# main.net
KiCad netlist of a schematic drawn in Altium Designer
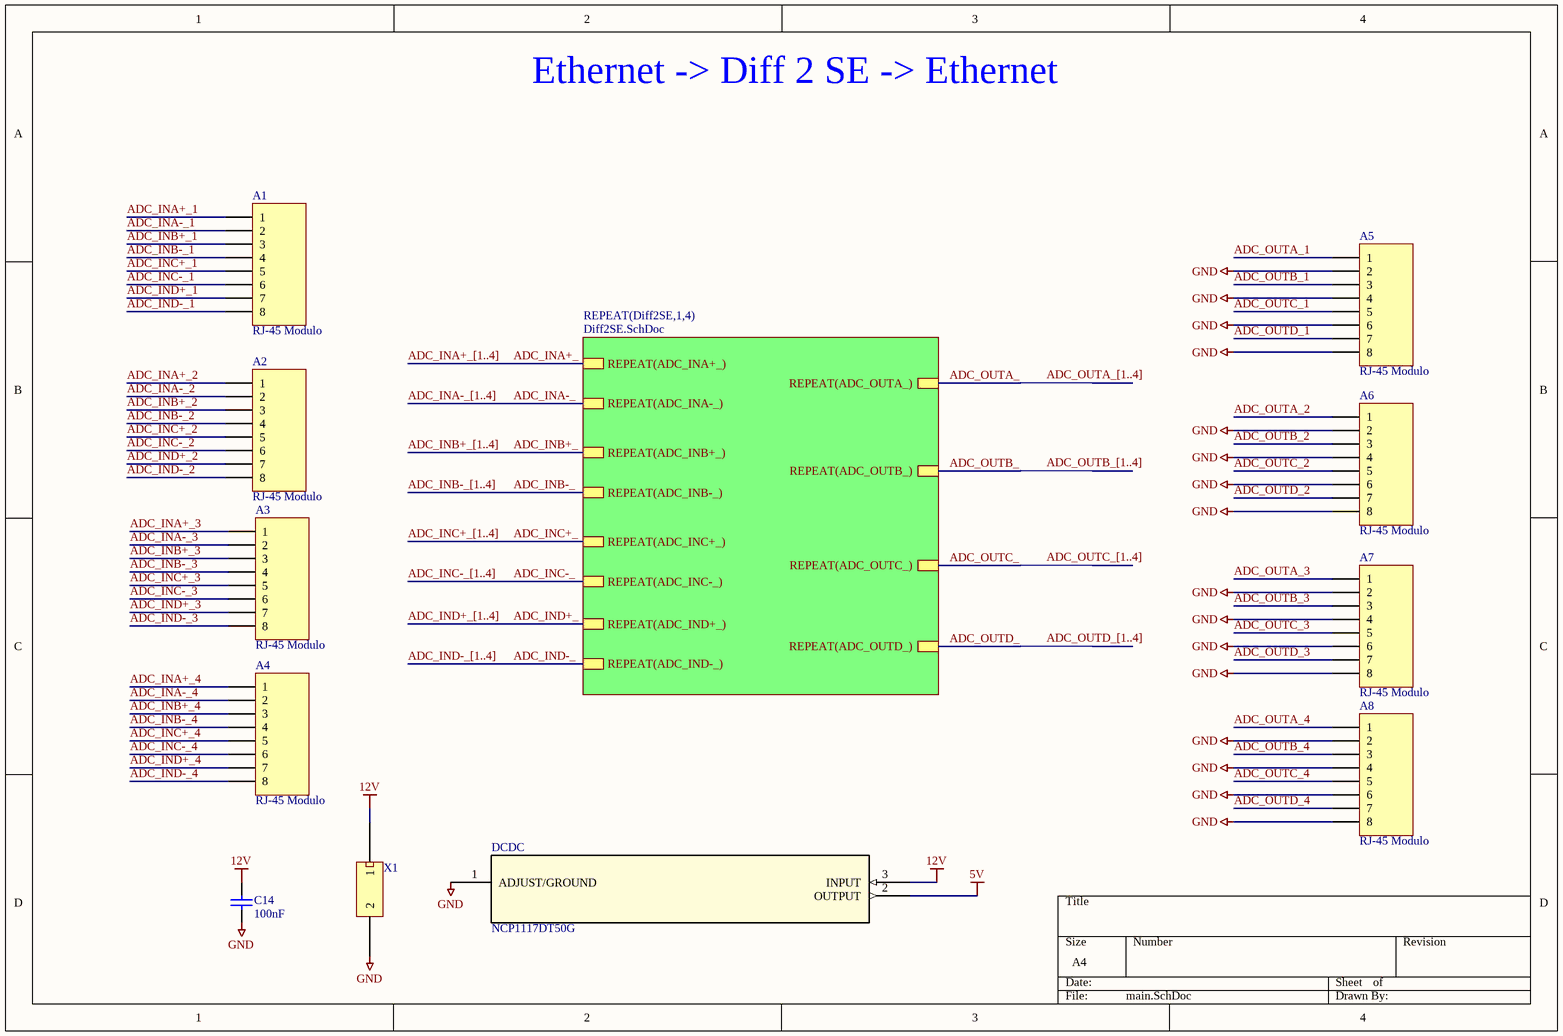
[diagram p0: main.SchDoc]

(export (version "E")
  (design (tool "Eeschema 10.0.6"))
  (components
    (comp (ref "A1")
      (value "RJ-45 Modulo")
      (footprint "RJ45_RJHSE5E80")
      (description "Modulo RJ-45 RJHSE5E80")
      (fields
        (field (name "MANUFACTURER") "Amphenol Commercial")
        (field (name "MANUFACTURER PART NUMBER") "RJHSE5E80")
        (field (name "PUBLISHER") "Altium Limited")
      )
      (libsource (lib "Schlib1") (part "RJ45_RJHSE5E80"))
    )
    (comp (ref "A2")
      (value "RJ-45 Modulo")
      (footprint "RJ45_RJHSE5E80")
      (description "Modulo RJ-45 RJHSE5E80")
      (fields
        (field (name "MANUFACTURER") "Amphenol Commercial")
        (field (name "MANUFACTURER PART NUMBER") "RJHSE5E80")
        (field (name "PUBLISHER") "Altium Limited")
      )
      (libsource (lib "Schlib1") (part "RJ45_RJHSE5E80"))
    )
    (comp (ref "A3")
      (value "RJ-45 Modulo")
      (footprint "RJ45_RJHSE5E80")
      (description "Modulo RJ-45 RJHSE5E80")
      (fields
        (field (name "MANUFACTURER") "Amphenol Commercial")
        (field (name "MANUFACTURER PART NUMBER") "RJHSE5E80")
        (field (name "PUBLISHER") "Altium Limited")
      )
      (libsource (lib "Schlib1") (part "RJ45_RJHSE5E80"))
    )
    (comp (ref "A4")
      (value "RJ-45 Modulo")
      (footprint "RJ45_RJHSE5E80")
      (description "Modulo RJ-45 RJHSE5E80")
      (fields
        (field (name "MANUFACTURER") "Amphenol Commercial")
        (field (name "MANUFACTURER PART NUMBER") "RJHSE5E80")
        (field (name "PUBLISHER") "Altium Limited")
      )
      (libsource (lib "Schlib1") (part "RJ45_RJHSE5E80"))
    )
    (comp (ref "A5")
      (value "RJ-45 Modulo")
      (footprint "RJ45_RJHSE5E80")
      (description "Modulo RJ-45 RJHSE5E80")
      (fields
        (field (name "MANUFACTURER") "Amphenol Commercial")
        (field (name "MANUFACTURER PART NUMBER") "RJHSE5E80")
        (field (name "PUBLISHER") "Altium Limited")
      )
      (libsource (lib "Schlib1") (part "RJ45_RJHSE5E80"))
    )
    (comp (ref "A6")
      (value "RJ-45 Modulo")
      (footprint "RJ45_RJHSE5E80")
      (description "Modulo RJ-45 RJHSE5E80")
      (fields
        (field (name "MANUFACTURER") "Amphenol Commercial")
        (field (name "MANUFACTURER PART NUMBER") "RJHSE5E80")
        (field (name "PUBLISHER") "Altium Limited")
      )
      (libsource (lib "Schlib1") (part "RJ45_RJHSE5E80"))
    )
    (comp (ref "A7")
      (value "RJ-45 Modulo")
      (footprint "RJ45_RJHSE5E80")
      (description "Modulo RJ-45 RJHSE5E80")
      (fields
        (field (name "MANUFACTURER") "Amphenol Commercial")
        (field (name "MANUFACTURER PART NUMBER") "RJHSE5E80")
        (field (name "PUBLISHER") "Altium Limited")
      )
      (libsource (lib "Schlib1") (part "RJ45_RJHSE5E80"))
    )
    (comp (ref "A8")
      (value "RJ-45 Modulo")
      (footprint "RJ45_RJHSE5E80")
      (description "Modulo RJ-45 RJHSE5E80")
      (fields
        (field (name "MANUFACTURER") "Amphenol Commercial")
        (field (name "MANUFACTURER PART NUMBER") "RJHSE5E80")
        (field (name "PUBLISHER") "Altium Limited")
      )
      (libsource (lib "Schlib1") (part "RJ45_RJHSE5E80"))
    )
    (comp (ref "C14")
      (value "100nF")
      (footprint "CAP_0805")
      (description "0.1µF ±10% 50V Ceramic Capacitor X7R 0805 (2012 Metric)")
      (fields (field (name "MF") "KEMET") (field (name "CREATED") "2020_06_15_DAarancibia"))
      (libsource (lib "Schlib1") (part "Cap_0805"))
    )
    (comp (ref "DCDC")
      (value "NCP1117DT50G")
      (footprint "DPAK_ONS")
      (description "No Description Available")
      (libsource (lib "Schlib1") (part "NCP1117DT50G"))
    )
    (comp (ref "X1")
      (value "Connector 2x1 R/A")
      (footprint "CON_WR-MPC4-649002227222")
      (description "Connector Header Through Hole, Right Angle 2 position 0.165\" (4.20mm)")
      (fields
        (field (name "MF") "Würth Elektronik")
        (field (name "MPN") "649002227222")
        (field (name "CREATED") "2020_06_14_DArancibia")
      )
      (libsource (lib "Schlib1") (part "Con_WR-MPC4_2x1"))
    )
  )
  (nets
    (net (code "2") (name "/ADC_INA+_1") (class "Default")
      (node (ref "A1") (pin "1") (pinfunction "1_1") (pintype "passive"))
    )
    (net (code "3") (name "/ADC_INA+_2") (class "Default")
      (node (ref "A2") (pin "1") (pinfunction "1_1") (pintype "passive"))
    )
    (net (code "4") (name "/ADC_INA+_3") (class "Default")
      (node (ref "A3") (pin "1") (pinfunction "1_1") (pintype "passive"))
    )
    (net (code "5") (name "/ADC_INA+_4") (class "Default")
      (node (ref "A4") (pin "1") (pinfunction "1_1") (pintype "passive"))
    )
    (net (code "8") (name "/ADC_INA-_1") (class "Default")
      (node (ref "A1") (pin "2") (pinfunction "2_2") (pintype "passive"))
    )
    (net (code "9") (name "/ADC_INA-_2") (class "Default")
      (node (ref "A2") (pin "2") (pinfunction "2_2") (pintype "passive"))
    )
    (net (code "10") (name "/ADC_INA-_3") (class "Default")
      (node (ref "A3") (pin "2") (pinfunction "2_2") (pintype "passive"))
    )
    (net (code "11") (name "/ADC_INA-_4") (class "Default")
      (node (ref "A4") (pin "2") (pinfunction "2_2") (pintype "passive"))
    )
    (net (code "14") (name "/ADC_INB+_1") (class "Default")
      (node (ref "A1") (pin "3") (pinfunction "3_3") (pintype "passive"))
    )
    (net (code "15") (name "/ADC_INB+_2") (class "Default")
      (node (ref "A2") (pin "3") (pinfunction "3_3") (pintype "passive"))
    )
    (net (code "16") (name "/ADC_INB+_3") (class "Default")
      (node (ref "A3") (pin "3") (pinfunction "3_3") (pintype "passive"))
    )
    (net (code "17") (name "/ADC_INB+_4") (class "Default")
      (node (ref "A4") (pin "3") (pinfunction "3_3") (pintype "passive"))
    )
    (net (code "20") (name "/ADC_INB-_1") (class "Default")
      (node (ref "A1") (pin "4") (pinfunction "4_4") (pintype "passive"))
    )
    (net (code "21") (name "/ADC_INB-_2") (class "Default")
      (node (ref "A2") (pin "4") (pinfunction "4_4") (pintype "passive"))
    )
    (net (code "22") (name "/ADC_INB-_3") (class "Default")
      (node (ref "A3") (pin "4") (pinfunction "4_4") (pintype "passive"))
    )
    (net (code "23") (name "/ADC_INB-_4") (class "Default")
      (node (ref "A4") (pin "4") (pinfunction "4_4") (pintype "passive"))
    )
    (net (code "26") (name "/ADC_INC+_1") (class "Default")
      (node (ref "A1") (pin "5") (pinfunction "5_5") (pintype "passive"))
    )
    (net (code "27") (name "/ADC_INC+_2") (class "Default")
      (node (ref "A2") (pin "5") (pinfunction "5_5") (pintype "passive"))
    )
    (net (code "28") (name "/ADC_INC+_3") (class "Default")
      (node (ref "A3") (pin "5") (pinfunction "5_5") (pintype "passive"))
    )
    (net (code "29") (name "/ADC_INC+_4") (class "Default")
      (node (ref "A4") (pin "5") (pinfunction "5_5") (pintype "passive"))
    )
    (net (code "32") (name "/ADC_INC-_1") (class "Default")
      (node (ref "A1") (pin "6") (pinfunction "6_6") (pintype "passive"))
    )
    (net (code "33") (name "/ADC_INC-_2") (class "Default")
      (node (ref "A2") (pin "6") (pinfunction "6_6") (pintype "passive"))
    )
    (net (code "34") (name "/ADC_INC-_3") (class "Default")
      (node (ref "A3") (pin "6") (pinfunction "6_6") (pintype "passive"))
    )
    (net (code "35") (name "/ADC_INC-_4") (class "Default")
      (node (ref "A4") (pin "6") (pinfunction "6_6") (pintype "passive"))
    )
    (net (code "38") (name "/ADC_IND+_1") (class "Default")
      (node (ref "A1") (pin "7") (pinfunction "7_7") (pintype "passive"))
    )
    (net (code "39") (name "/ADC_IND+_2") (class "Default")
      (node (ref "A2") (pin "7") (pinfunction "7_7") (pintype "passive"))
    )
    (net (code "40") (name "/ADC_IND+_3") (class "Default")
      (node (ref "A3") (pin "7") (pinfunction "7_7") (pintype "passive"))
    )
    (net (code "41") (name "/ADC_IND+_4") (class "Default")
      (node (ref "A4") (pin "7") (pinfunction "7_7") (pintype "passive"))
    )
    (net (code "44") (name "/ADC_IND-_1") (class "Default")
      (node (ref "A1") (pin "8") (pinfunction "8_8") (pintype "passive"))
    )
    (net (code "45") (name "/ADC_IND-_2") (class "Default")
      (node (ref "A2") (pin "8") (pinfunction "8_8") (pintype "passive"))
    )
    (net (code "46") (name "/ADC_IND-_3") (class "Default")
      (node (ref "A3") (pin "8") (pinfunction "8_8") (pintype "passive"))
    )
    (net (code "47") (name "/ADC_IND-_4") (class "Default")
      (node (ref "A4") (pin "8") (pinfunction "8_8") (pintype "passive"))
    )
    (net (code "50") (name "/ADC_OUTA_1") (class "Default")
      (node (ref "A5") (pin "1") (pinfunction "1_1") (pintype "passive"))
    )
    (net (code "51") (name "/ADC_OUTA_2") (class "Default")
      (node (ref "A6") (pin "1") (pinfunction "1_1") (pintype "passive"))
    )
    (net (code "52") (name "/ADC_OUTA_3") (class "Default")
      (node (ref "A7") (pin "1") (pinfunction "1_1") (pintype "passive"))
    )
    (net (code "53") (name "/ADC_OUTA_4") (class "Default")
      (node (ref "A8") (pin "1") (pinfunction "1_1") (pintype "passive"))
    )
    (net (code "56") (name "/ADC_OUTB_1") (class "Default")
      (node (ref "A5") (pin "3") (pinfunction "3_3") (pintype "passive"))
    )
    (net (code "57") (name "/ADC_OUTB_2") (class "Default")
      (node (ref "A6") (pin "3") (pinfunction "3_3") (pintype "passive"))
    )
    (net (code "58") (name "/ADC_OUTB_3") (class "Default")
      (node (ref "A7") (pin "3") (pinfunction "3_3") (pintype "passive"))
    )
    (net (code "59") (name "/ADC_OUTB_4") (class "Default")
      (node (ref "A8") (pin "3") (pinfunction "3_3") (pintype "passive"))
    )
    (net (code "62") (name "/ADC_OUTC_1") (class "Default")
      (node (ref "A5") (pin "5") (pinfunction "5_5") (pintype "passive"))
    )
    (net (code "63") (name "/ADC_OUTC_2") (class "Default")
      (node (ref "A6") (pin "5") (pinfunction "5_5") (pintype "passive"))
    )
    (net (code "64") (name "/ADC_OUTC_3") (class "Default")
      (node (ref "A7") (pin "5") (pinfunction "5_5") (pintype "passive"))
    )
    (net (code "65") (name "/ADC_OUTC_4") (class "Default")
      (node (ref "A8") (pin "5") (pinfunction "5_5") (pintype "passive"))
    )
    (net (code "68") (name "/ADC_OUTD_1") (class "Default")
      (node (ref "A5") (pin "7") (pinfunction "7_7") (pintype "passive"))
    )
    (net (code "69") (name "/ADC_OUTD_2") (class "Default")
      (node (ref "A6") (pin "7") (pinfunction "7_7") (pintype "passive"))
    )
    (net (code "70") (name "/ADC_OUTD_3") (class "Default")
      (node (ref "A7") (pin "7") (pinfunction "7_7") (pintype "passive"))
    )
    (net (code "71") (name "/ADC_OUTD_4") (class "Default")
      (node (ref "A8") (pin "7") (pinfunction "7_7") (pintype "passive"))
    )
    (net (code "73") (name "5V") (class "Default")
      (node (ref "DCDC") (pin "2") (pinfunction "OUTPUT_2") (pintype "output"))
    )
    (net (code "74") (name "12V") (class "Default")
      (node (ref "C14") (pin "1") (pinfunction "1_1") (pintype "passive"))
      (node (ref "DCDC") (pin "3") (pinfunction "INPUT_3") (pintype "input"))
      (node (ref "X1") (pin "1") (pinfunction "1_1") (pintype "passive"))
    )
    (net (code "75") (name "GND") (class "Default")
      (node (ref "A5") (pin "2") (pinfunction "2_2") (pintype "passive"))
      (node (ref "A5") (pin "4") (pinfunction "4_4") (pintype "passive"))
      (node (ref "A5") (pin "6") (pinfunction "6_6") (pintype "passive"))
      (node (ref "A5") (pin "8") (pinfunction "8_8") (pintype "passive"))
      (node (ref "A6") (pin "2") (pinfunction "2_2") (pintype "passive"))
      (node (ref "A6") (pin "4") (pinfunction "4_4") (pintype "passive"))
      (node (ref "A6") (pin "6") (pinfunction "6_6") (pintype "passive"))
      (node (ref "A6") (pin "8") (pinfunction "8_8") (pintype "passive"))
      (node (ref "A7") (pin "2") (pinfunction "2_2") (pintype "passive"))
      (node (ref "A7") (pin "4") (pinfunction "4_4") (pintype "passive"))
      (node (ref "A7") (pin "6") (pinfunction "6_6") (pintype "passive"))
      (node (ref "A7") (pin "8") (pinfunction "8_8") (pintype "passive"))
      (node (ref "A8") (pin "2") (pinfunction "2_2") (pintype "passive"))
      (node (ref "A8") (pin "4") (pinfunction "4_4") (pintype "passive"))
      (node (ref "A8") (pin "6") (pinfunction "6_6") (pintype "passive"))
      (node (ref "A8") (pin "8") (pinfunction "8_8") (pintype "passive"))
      (node (ref "C14") (pin "2") (pinfunction "2_2") (pintype "passive"))
      (node (ref "DCDC") (pin "1") (pinfunction "ADJUST/GROUND_1") (pintype "passive"))
      (node (ref "X1") (pin "2") (pinfunction "2_2") (pintype "passive"))
    )
  )
)
